# Sheet1.net
KiCad netlist of a schematic drawn in Altium Designer
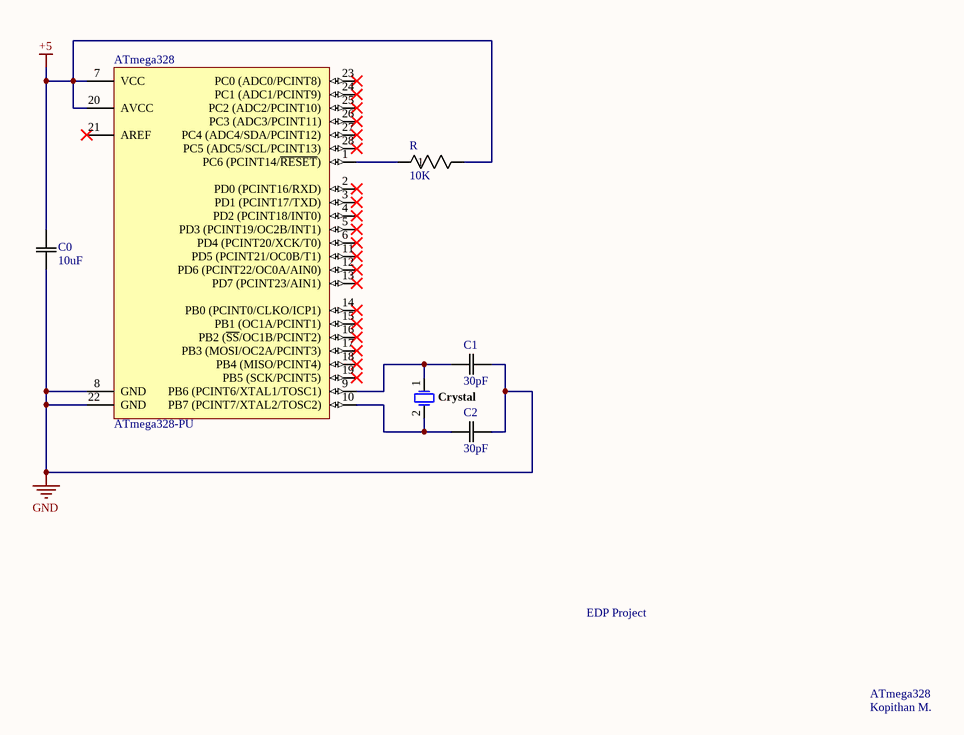
[diagram p0: Sheet1.SchDoc]

(export (version "E")
  (design (tool "Eeschema 10.0.6"))
  (components
    (comp (ref "ATmega328")
      (value "ATmega328-PU")
      (footprint "28P3")
      (libsource (lib "Altium Content Vault") (part "MC-8B-ATM48-IL28"))
    )
    (comp (ref "C0")
      (value "10uF")
      (footprint "CAP_WCAP-PTHR_6P3X8P0_WRE")
      (libsource (lib "870055673001") (part "870055673001"))
    )
    (comp (ref "C1")
      (value "30pF")
      (footprint "CAP_CD15_CND")
      (description "CD15ED300JO3F")
      (libsource (lib "CD15ED300JO3F") (part "CD15ED300JO3F"))
    )
    (comp (ref "C2")
      (value "30pF")
      (footprint "CAP_CD15_CND")
      (description "CD15ED300JO3F")
      (libsource (lib "CD15ED300JO3F") (part "CD15ED300JO3F"))
    )
    (comp (ref "Crystal")
      (value "FOXSLF/160-20")
      (footprint "FOX-FOXSLF160-20")
      (description "Resistance Weld Thru-Hole Crystal, 16 MHz, -20 to 70 degC, 2-Pin THD, RoHS, Bulk")
      (fields (field (name "TOLERANCE") "1%"))
      (libsource (lib "Altium Content Vault") (part "XTAL-1-2-2"))
    )
    (comp (ref "R")
      (value "10K")
      (footprint "RES_TYCO_YR1_TYC")
      (description "30pF")
      (libsource (lib "YR1B10KCC") (part "YR1B10KCC"))
    )
  )
  (nets
    (net (code "1") (name "+5") (class "Default")
      (node (ref "ATmega328") (pin "20") (pinfunction "AVCC_20") (pintype "power_in"))
      (node (ref "ATmega328") (pin "7") (pinfunction "VCC_7") (pintype "power_in"))
      (node (ref "C0") (pin "2") (pinfunction "2_2") (pintype "passive"))
      (node (ref "R") (pin "2") (pinfunction "2_2") (pintype "passive"))
    )
    (net (code "2") (name "GND") (class "Default")
      (node (ref "ATmega328") (pin "22") (pinfunction "GND_22") (pintype "power_in"))
      (node (ref "ATmega328") (pin "8") (pinfunction "GND_8") (pintype "power_in"))
      (node (ref "C0") (pin "1") (pinfunction "1_1") (pintype "passive"))
      (node (ref "C1") (pin "2") (pinfunction "2_2") (pintype "passive"))
      (node (ref "C2") (pin "2") (pinfunction "2_2") (pintype "passive"))
    )
    (net (code "3") (name "Net-(ATmega328-PB6_(PCINT6{slash}XTAL1{slash}TOSC1))") (class "Default")
      (node (ref "ATmega328") (pin "9") (pinfunction "PB6_(PCINT6/XTAL1/TOSC1)_9") (pintype "bidirectional"))
      (node (ref "C1") (pin "1") (pinfunction "1_1") (pintype "passive"))
      (node (ref "Crystal") (pin "1") (pinfunction "1_1") (pintype "passive"))
    )
    (net (code "4") (name "Net-(ATmega328-PB7_(PCINT7{slash}XTAL2{slash}TOSC2))") (class "Default")
      (node (ref "ATmega328") (pin "10") (pinfunction "PB7_(PCINT7/XTAL2/TOSC2)_10") (pintype "bidirectional"))
      (node (ref "C2") (pin "1") (pinfunction "1_1") (pintype "passive"))
      (node (ref "Crystal") (pin "2") (pinfunction "2_2") (pintype "passive"))
    )
    (net (code "5") (name "Net-(ATmega328-PC6_(PCINT14{slash}~{RESET}))") (class "Default")
      (node (ref "ATmega328") (pin "1") (pinfunction "PC6_(PCINT14/~{RESET})_1") (pintype "bidirectional"))
      (node (ref "R") (pin "1") (pinfunction "1_1") (pintype "passive"))
    )
    (net (code "6") (name "unconnected-(ATmega328-AREF-Pad21)") (class "Default")
      (node (ref "ATmega328") (pin "21") (pinfunction "AREF_21") (pintype "power_in+no_connect"))
    )
    (net (code "7") (name "unconnected-(ATmega328-PB0_(PCINT0{slash}CLKO{slash}ICP1)-Pad14)") (class "Default")
      (node (ref "ATmega328") (pin "14") (pinfunction "PB0_(PCINT0/CLKO/ICP1)_14") (pintype "bidirectional+no_connect"))
    )
    (net (code "8") (name "unconnected-(ATmega328-PB1_(OC1A{slash}PCINT1)-Pad15)") (class "Default")
      (node (ref "ATmega328") (pin "15") (pinfunction "PB1_(OC1A/PCINT1)_15") (pintype "bidirectional+no_connect"))
    )
    (net (code "9") (name "unconnected-(ATmega328-PB2_(~{SS}{slash}OC1B{slash}PCINT2)-Pad16)") (class "Default")
      (node (ref "ATmega328") (pin "16") (pinfunction "PB2_(~{SS}/OC1B/PCINT2)_16") (pintype "bidirectional+no_connect"))
    )
    (net (code "10") (name "unconnected-(ATmega328-PB3_(MOSI{slash}OC2A{slash}PCINT3)-Pad17)") (class "Default")
      (node (ref "ATmega328") (pin "17") (pinfunction "PB3_(MOSI/OC2A/PCINT3)_17") (pintype "bidirectional+no_connect"))
    )
    (net (code "11") (name "unconnected-(ATmega328-PB4_(MISO{slash}PCINT4)-Pad18)") (class "Default")
      (node (ref "ATmega328") (pin "18") (pinfunction "PB4_(MISO/PCINT4)_18") (pintype "bidirectional+no_connect"))
    )
    (net (code "12") (name "unconnected-(ATmega328-PB5_(SCK{slash}PCINT5)-Pad19)") (class "Default")
      (node (ref "ATmega328") (pin "19") (pinfunction "PB5_(SCK/PCINT5)_19") (pintype "bidirectional+no_connect"))
    )
    (net (code "13") (name "unconnected-(ATmega328-PC0_(ADC0{slash}PCINT8)-Pad23)") (class "Default")
      (node (ref "ATmega328") (pin "23") (pinfunction "PC0_(ADC0/PCINT8)_23") (pintype "bidirectional+no_connect"))
    )
    (net (code "14") (name "unconnected-(ATmega328-PC1_(ADC1{slash}PCINT9)-Pad24)") (class "Default")
      (node (ref "ATmega328") (pin "24") (pinfunction "PC1_(ADC1/PCINT9)_24") (pintype "bidirectional+no_connect"))
    )
    (net (code "15") (name "unconnected-(ATmega328-PC2_(ADC2{slash}PCINT10)-Pad25)") (class "Default")
      (node (ref "ATmega328") (pin "25") (pinfunction "PC2_(ADC2/PCINT10)_25") (pintype "bidirectional+no_connect"))
    )
    (net (code "16") (name "unconnected-(ATmega328-PC3_(ADC3{slash}PCINT11)-Pad26)") (class "Default")
      (node (ref "ATmega328") (pin "26") (pinfunction "PC3_(ADC3/PCINT11)_26") (pintype "bidirectional+no_connect"))
    )
    (net (code "17") (name "unconnected-(ATmega328-PC4_(ADC4{slash}SDA{slash}PCINT12)-Pad27)") (class "Default")
      (node (ref "ATmega328") (pin "27") (pinfunction "PC4_(ADC4/SDA/PCINT12)_27") (pintype "bidirectional+no_connect"))
    )
    (net (code "18") (name "unconnected-(ATmega328-PC5_(ADC5{slash}SCL{slash}PCINT13)-Pad28)") (class "Default")
      (node (ref "ATmega328") (pin "28") (pinfunction "PC5_(ADC5/SCL/PCINT13)_28") (pintype "bidirectional+no_connect"))
    )
    (net (code "19") (name "unconnected-(ATmega328-PD0_(PCINT16{slash}RXD)-Pad2)") (class "Default")
      (node (ref "ATmega328") (pin "2") (pinfunction "PD0_(PCINT16/RXD)_2") (pintype "bidirectional+no_connect"))
    )
    (net (code "20") (name "unconnected-(ATmega328-PD1_(PCINT17{slash}TXD)-Pad3)") (class "Default")
      (node (ref "ATmega328") (pin "3") (pinfunction "PD1_(PCINT17/TXD)_3") (pintype "bidirectional+no_connect"))
    )
    (net (code "21") (name "unconnected-(ATmega328-PD2_(PCINT18{slash}INT0)-Pad4)") (class "Default")
      (node (ref "ATmega328") (pin "4") (pinfunction "PD2_(PCINT18/INT0)_4") (pintype "bidirectional+no_connect"))
    )
    (net (code "22") (name "unconnected-(ATmega328-PD3_(PCINT19{slash}OC2B{slash}INT1)-Pad5)") (class "Default")
      (node (ref "ATmega328") (pin "5") (pinfunction "PD3_(PCINT19/OC2B/INT1)_5") (pintype "bidirectional+no_connect"))
    )
    (net (code "23") (name "unconnected-(ATmega328-PD4_(PCINT20{slash}XCK{slash}T0)-Pad6)") (class "Default")
      (node (ref "ATmega328") (pin "6") (pinfunction "PD4_(PCINT20/XCK/T0)_6") (pintype "bidirectional+no_connect"))
    )
    (net (code "24") (name "unconnected-(ATmega328-PD5_(PCINT21{slash}OC0B{slash}T1)-Pad11)") (class "Default")
      (node (ref "ATmega328") (pin "11") (pinfunction "PD5_(PCINT21/OC0B/T1)_11") (pintype "bidirectional+no_connect"))
    )
    (net (code "25") (name "unconnected-(ATmega328-PD6_(PCINT22{slash}OC0A{slash}AIN0)-Pad12)") (class "Default")
      (node (ref "ATmega328") (pin "12") (pinfunction "PD6_(PCINT22/OC0A/AIN0)_12") (pintype "bidirectional+no_connect"))
    )
    (net (code "26") (name "unconnected-(ATmega328-PD7_(PCINT23{slash}AIN1)-Pad13)") (class "Default")
      (node (ref "ATmega328") (pin "13") (pinfunction "PD7_(PCINT23/AIN1)_13") (pintype "bidirectional+no_connect"))
    )
  )
)
